# M452sx.net
KiCad netlist of a schematic drawn in EAGLE
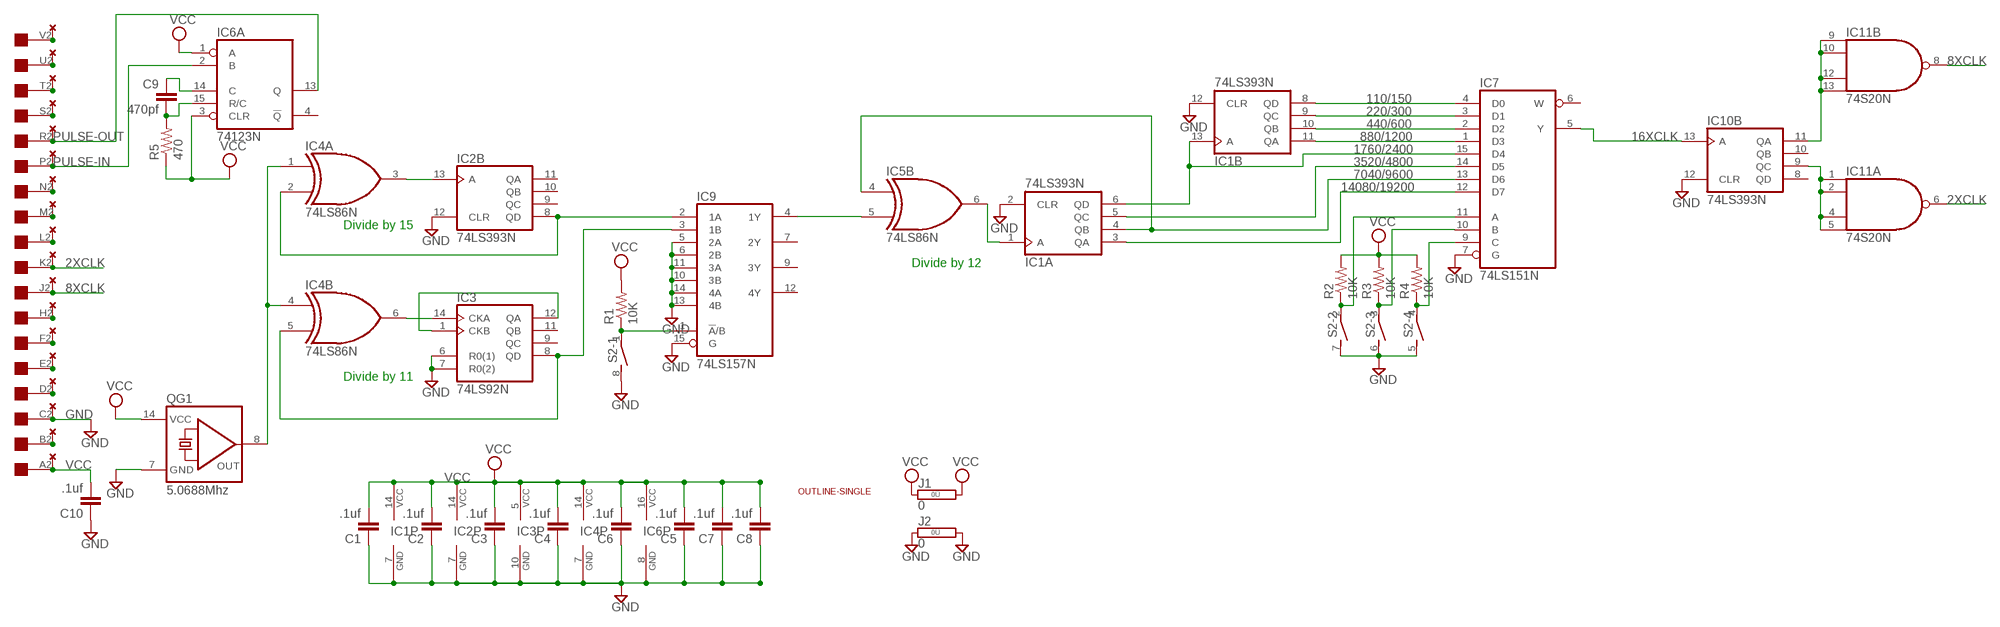
[diagram p0: schematic, sheet 1]

(export (version "E")
  (design (tool "Eeschema 10.0.6"))
  (components
    (comp (ref "C1")
      (value ".1uf")
      (footprint "eagle-import:C050-025X075")
      (libsource (lib "eagle-import") (part "C-EU050-025X075"))
    )
    (comp (ref "C2")
      (value ".1uf")
      (footprint "eagle-import:C050-025X075")
      (libsource (lib "eagle-import") (part "C-EU050-025X075"))
    )
    (comp (ref "C3")
      (value ".1uf")
      (footprint "eagle-import:C050-025X075")
      (libsource (lib "eagle-import") (part "C-EU050-025X075"))
    )
    (comp (ref "C4")
      (value ".1uf")
      (footprint "eagle-import:C050-025X075")
      (libsource (lib "eagle-import") (part "C-EU050-025X075"))
    )
    (comp (ref "C5")
      (value ".1uf")
      (footprint "eagle-import:C050-025X075")
      (libsource (lib "eagle-import") (part "C-EU050-025X075"))
    )
    (comp (ref "C6")
      (value ".1uf")
      (footprint "eagle-import:C050-025X075")
      (libsource (lib "eagle-import") (part "C-EU050-025X075"))
    )
    (comp (ref "C7")
      (value ".1uf")
      (footprint "eagle-import:C050-025X075")
      (libsource (lib "eagle-import") (part "C-EU050-025X075"))
    )
    (comp (ref "C8")
      (value ".1uf")
      (footprint "eagle-import:C050-025X075")
      (libsource (lib "eagle-import") (part "C-EU050-025X075"))
    )
    (comp (ref "C9")
      (value "470pf")
      (footprint "eagle-import:C050-025X075")
      (libsource (lib "eagle-import") (part "C-EU050-025X075"))
    )
    (comp (ref "C10")
      (value ".1uf")
      (footprint "eagle-import:C050-025X075")
      (libsource (lib "eagle-import") (part "C-EU050-025X075"))
    )
    (comp (ref "IC1")
      (value "74LS393N")
      (footprint "eagle-import:DIL14")
      (libsource (lib "eagle-import") (part "74393NLS"))
    )
    (comp (ref "IC2")
      (value "74LS393N")
      (footprint "eagle-import:DIL14")
      (libsource (lib "eagle-import") (part "74393NLS"))
    )
    (comp (ref "IC3")
      (value "74LS92N")
      (footprint "eagle-import:DIL14")
      (libsource (lib "eagle-import") (part "7492NLS"))
    )
    (comp (ref "IC4")
      (value "74LS86N")
      (footprint "eagle-import:DIL14")
      (libsource (lib "eagle-import") (part "7486NLS"))
    )
    (comp (ref "IC5")
      (value "74LS86N")
      (footprint "eagle-import:DIL14")
      (libsource (lib "eagle-import") (part "7486NLS"))
    )
    (comp (ref "IC6")
      (value "74123N")
      (footprint "eagle-import:DIL16")
      (libsource (lib "eagle-import") (part "74123N"))
    )
    (comp (ref "IC7")
      (value "74LS151N")
      (footprint "eagle-import:DIL16")
      (libsource (lib "eagle-import") (part "74151N"))
    )
    (comp (ref "IC9")
      (value "74LS157N")
      (footprint "eagle-import:DIL16")
      (libsource (lib "eagle-import") (part "74157NLS"))
    )
    (comp (ref "IC10")
      (value "74LS393N")
      (footprint "eagle-import:DIL14")
      (libsource (lib "eagle-import") (part "74393NLS"))
    )
    (comp (ref "IC11")
      (value "74S20N")
      (footprint "eagle-import:DIL14")
      (libsource (lib "eagle-import") (part "7420NS"))
    )
    (comp (ref "J1")
      (value "0")
      (footprint "eagle-import:0R_10")
      (libsource (lib "eagle-import") (part "0R"))
    )
    (comp (ref "J2")
      (value "0")
      (footprint "eagle-import:0R_10")
      (libsource (lib "eagle-import") (part "0R"))
    )
    (comp (ref "QG1")
      (value "5.0688Mhz")
      (footprint "eagle-import:DIL14S")
      (libsource (lib "eagle-import") (part "QG5860"))
    )
    (comp (ref "R1")
      (value "10K")
      (footprint "eagle-import:0204_7")
      (libsource (lib "eagle-import") (part "R-US_0204/7"))
    )
    (comp (ref "R2")
      (value "10K")
      (footprint "eagle-import:0204_7")
      (libsource (lib "eagle-import") (part "R-US_0204/7"))
    )
    (comp (ref "R3")
      (value "10K")
      (footprint "eagle-import:0204_7")
      (libsource (lib "eagle-import") (part "R-US_0204/7"))
    )
    (comp (ref "R4")
      (value "10K")
      (footprint "eagle-import:0204_7")
      (libsource (lib "eagle-import") (part "R-US_0204/7"))
    )
    (comp (ref "R5")
      (value "470")
      (footprint "eagle-import:0204_7")
      (libsource (lib "eagle-import") (part "R-US_0204/7"))
    )
    (comp (ref "S2")
      (value "DIP04S")
      (footprint "eagle-import:DIP04S")
      (libsource (lib "eagle-import") (part "DIP04S"))
    )
    (comp (ref "U$2")
      (value "THRU-HOLE1")
      (footprint "eagle-import:THRU-HOLE1")
      (libsource (lib "eagle-import") (part "THRU-HOLE1"))
    )
    (comp (ref "U$3")
      (value "OUTLINE-SINGLE")
      (footprint "eagle-import:SINGLE")
      (libsource (lib "eagle-import") (part "OUTLINE-SINGLE"))
    )
    (comp (ref "U$4")
      (value "EDGE-1")
      (footprint "eagle-import:EDGE-CON1")
      (libsource (lib "eagle-import") (part "EDGE-1"))
    )
  )
  (nets
    (net (code "1") (name "/2XCLK") (class "Default")
      (node (ref "IC11") (pin "6") (pinfunction "O_6") (pintype "output"))
      (node (ref "U$2") (pin "K2") (pinfunction "P$1_K2") (pintype "passive"))
      (node (ref "U$4") (pin "K2") (pinfunction "1_K2") (pintype "bidirectional"))
    )
    (net (code "2") (name "/8XCLK") (class "Default")
      (node (ref "IC11") (pin "8") (pinfunction "O_8") (pintype "output"))
      (node (ref "U$2") (pin "J2") (pinfunction "P$1_J2") (pintype "passive"))
      (node (ref "U$4") (pin "J2") (pinfunction "1_J2") (pintype "bidirectional"))
    )
    (net (code "3") (name "/16XCLK") (class "Default")
      (node (ref "IC10") (pin "13") (pinfunction "A_13") (pintype "input"))
      (node (ref "IC7") (pin "5") (pinfunction "Y_5") (pintype "output"))
    )
    (net (code "4") (name "/110{slash}150") (class "Default")
      (node (ref "IC1") (pin "8") (pinfunction "QD_8") (pintype "output"))
      (node (ref "IC7") (pin "4") (pinfunction "D0_4") (pintype "input"))
    )
    (net (code "5") (name "/220{slash}300") (class "Default")
      (node (ref "IC1") (pin "9") (pinfunction "QC_9") (pintype "output"))
      (node (ref "IC7") (pin "3") (pinfunction "D1_3") (pintype "input"))
    )
    (net (code "6") (name "/440{slash}600") (class "Default")
      (node (ref "IC1") (pin "10") (pinfunction "QB_10") (pintype "output"))
      (node (ref "IC7") (pin "2") (pinfunction "D2_2") (pintype "input"))
    )
    (net (code "7") (name "/880{slash}1200") (class "Default")
      (node (ref "IC1") (pin "11") (pinfunction "QA_11") (pintype "output"))
      (node (ref "IC7") (pin "1") (pinfunction "D3_1") (pintype "input"))
    )
    (net (code "8") (name "/1760{slash}2400") (class "Default")
      (node (ref "IC1") (pin "13") (pinfunction "A_13") (pintype "input"))
      (node (ref "IC1") (pin "6") (pinfunction "QD_6") (pintype "output"))
      (node (ref "IC7") (pin "15") (pinfunction "D4_15") (pintype "input"))
    )
    (net (code "9") (name "/3520{slash}4800") (class "Default")
      (node (ref "IC1") (pin "5") (pinfunction "QC_5") (pintype "output"))
      (node (ref "IC7") (pin "14") (pinfunction "D5_14") (pintype "input"))
    )
    (net (code "10") (name "/7040{slash}9600") (class "Default")
      (node (ref "IC1") (pin "4") (pinfunction "QB_4") (pintype "output"))
      (node (ref "IC5") (pin "4") (pinfunction "I0_4") (pintype "input"))
      (node (ref "IC7") (pin "13") (pinfunction "D6_13") (pintype "input"))
    )
    (net (code "11") (name "/14080{slash}19200") (class "Default")
      (node (ref "IC1") (pin "3") (pinfunction "QA_3") (pintype "output"))
      (node (ref "IC7") (pin "12") (pinfunction "D7_12") (pintype "input"))
    )
    (net (code "12") (name "/PULSE-IN") (class "Default")
      (node (ref "IC6") (pin "2") (pinfunction "B_2") (pintype "input"))
      (node (ref "U$2") (pin "P2") (pinfunction "P$1_P2") (pintype "passive"))
      (node (ref "U$4") (pin "P2") (pinfunction "1_P2") (pintype "bidirectional"))
    )
    (net (code "13") (name "/PULSE-OUT") (class "Default")
      (node (ref "IC6") (pin "13") (pinfunction "Q_13") (pintype "output"))
      (node (ref "U$2") (pin "R2") (pinfunction "P$1_R2") (pintype "passive"))
      (node (ref "U$4") (pin "R2") (pinfunction "1_R2") (pintype "bidirectional"))
    )
    (net (code "14") (name "GND") (class "Default")
      (node (ref "C1") (pin "1") (pinfunction "1_1") (pintype "passive"))
      (node (ref "C10") (pin "1") (pinfunction "1_1") (pintype "passive"))
      (node (ref "C2") (pin "1") (pinfunction "1_1") (pintype "passive"))
      (node (ref "C3") (pin "1") (pinfunction "1_1") (pintype "passive"))
      (node (ref "C4") (pin "1") (pinfunction "1_1") (pintype "passive"))
      (node (ref "C5") (pin "1") (pinfunction "1_1") (pintype "passive"))
      (node (ref "C6") (pin "1") (pinfunction "1_1") (pintype "passive"))
      (node (ref "C7") (pin "1") (pinfunction "1_1") (pintype "passive"))
      (node (ref "C8") (pin "1") (pinfunction "1_1") (pintype "passive"))
      (node (ref "IC1") (pin "12") (pinfunction "CLR_12") (pintype "input"))
      (node (ref "IC1") (pin "2") (pinfunction "CLR_2") (pintype "input"))
      (node (ref "IC1") (pin "7") (pinfunction "GND_7") (pintype "power_in"))
      (node (ref "IC10") (pin "12") (pinfunction "CLR_12") (pintype "input"))
      (node (ref "IC2") (pin "12") (pinfunction "CLR_12") (pintype "input"))
      (node (ref "IC2") (pin "7") (pinfunction "GND_7") (pintype "power_in"))
      (node (ref "IC3") (pin "10") (pinfunction "GND_10") (pintype "power_in"))
      (node (ref "IC3") (pin "6") (pinfunction "R0(1)_6") (pintype "input"))
      (node (ref "IC3") (pin "7") (pinfunction "R0(2)_7") (pintype "input"))
      (node (ref "IC4") (pin "7") (pinfunction "GND_7") (pintype "power_in"))
      (node (ref "IC6") (pin "8") (pinfunction "GND_8") (pintype "power_in"))
      (node (ref "IC7") (pin "7") (pinfunction "G_7") (pintype "input"))
      (node (ref "IC9") (pin "10") (pinfunction "3B_10") (pintype "input"))
      (node (ref "IC9") (pin "11") (pinfunction "3A_11") (pintype "input"))
      (node (ref "IC9") (pin "13") (pinfunction "4B_13") (pintype "input"))
      (node (ref "IC9") (pin "14") (pinfunction "4A_14") (pintype "input"))
      (node (ref "IC9") (pin "15") (pinfunction "G_15") (pintype "input"))
      (node (ref "IC9") (pin "5") (pinfunction "2A_5") (pintype "input"))
      (node (ref "IC9") (pin "6") (pinfunction "2B_6") (pintype "input"))
      (node (ref "J2") (pin "1") (pinfunction "1_1") (pintype "passive"))
      (node (ref "J2") (pin "2") (pinfunction "2_2") (pintype "passive"))
      (node (ref "QG1") (pin "7") (pinfunction "GND_7") (pintype "power_in"))
      (node (ref "S2") (pin "5") (pinfunction "2_5") (pintype "passive"))
      (node (ref "S2") (pin "6") (pinfunction "2_6") (pintype "passive"))
      (node (ref "S2") (pin "7") (pinfunction "2_7") (pintype "passive"))
      (node (ref "S2") (pin "8") (pinfunction "2_8") (pintype "passive"))
      (node (ref "U$2") (pin "C2") (pinfunction "P$1_C2") (pintype "passive"))
      (node (ref "U$4") (pin "C2") (pinfunction "1_C2") (pintype "bidirectional"))
    )
    (net (code "15") (name "Net-(IC1A-A)") (class "Default")
      (node (ref "IC1") (pin "1") (pinfunction "A_1") (pintype "input"))
      (node (ref "IC5") (pin "6") (pinfunction "O_6") (pintype "output"))
    )
    (net (code "16") (name "Net-(IC2B-A)") (class "Default")
      (node (ref "IC2") (pin "13") (pinfunction "A_13") (pintype "input"))
      (node (ref "IC4") (pin "3") (pinfunction "O_3") (pintype "output"))
    )
    (net (code "17") (name "Net-(IC2B-QD)") (class "Default")
      (node (ref "IC2") (pin "8") (pinfunction "QD_8") (pintype "output"))
      (node (ref "IC4") (pin "2") (pinfunction "I1_2") (pintype "input"))
      (node (ref "IC9") (pin "2") (pinfunction "1A_2") (pintype "input"))
    )
    (net (code "18") (name "Net-(IC3A-CKA)") (class "Default")
      (node (ref "IC3") (pin "14") (pinfunction "CKA_14") (pintype "input"))
      (node (ref "IC4") (pin "6") (pinfunction "O_6") (pintype "output"))
    )
    (net (code "19") (name "Net-(IC3A-CKB)") (class "Default")
      (node (ref "IC3") (pin "1") (pinfunction "CKB_1") (pintype "input"))
      (node (ref "IC3") (pin "12") (pinfunction "QA_12") (pintype "output"))
    )
    (net (code "20") (name "Net-(IC3A-QD)") (class "Default")
      (node (ref "IC3") (pin "8") (pinfunction "QD_8") (pintype "output"))
      (node (ref "IC4") (pin "5") (pinfunction "I1_5") (pintype "input"))
      (node (ref "IC9") (pin "3") (pinfunction "1B_3") (pintype "input"))
    )
    (net (code "21") (name "Net-(IC4A-I0)") (class "Default")
      (node (ref "IC4") (pin "1") (pinfunction "I0_1") (pintype "input"))
      (node (ref "IC4") (pin "4") (pinfunction "I0_4") (pintype "input"))
      (node (ref "QG1") (pin "8") (pinfunction "OUT_8") (pintype "output"))
    )
    (net (code "22") (name "Net-(IC5B-I1)") (class "Default")
      (node (ref "IC5") (pin "5") (pinfunction "I1_5") (pintype "input"))
      (node (ref "IC9") (pin "4") (pinfunction "1Y_4") (pintype "output"))
    )
    (net (code "23") (name "Net-(IC6A-C)") (class "Default")
      (node (ref "C9") (pin "1") (pinfunction "1_1") (pintype "passive"))
      (node (ref "IC6") (pin "14") (pinfunction "C_14") (pintype "input"))
    )
    (net (code "24") (name "Net-(IC6A-R{slash}C)") (class "Default")
      (node (ref "C9") (pin "2") (pinfunction "2_2") (pintype "passive"))
      (node (ref "IC6") (pin "15") (pinfunction "R/C_15") (pintype "input"))
      (node (ref "R5") (pin "2") (pinfunction "2_2") (pintype "passive"))
    )
    (net (code "25") (name "Net-(IC7A-A)") (class "Default")
      (node (ref "IC7") (pin "11") (pinfunction "A_11") (pintype "input"))
      (node (ref "R2") (pin "1") (pinfunction "1_1") (pintype "passive"))
      (node (ref "S2") (pin "2") (pinfunction "1_2") (pintype "passive"))
    )
    (net (code "26") (name "Net-(IC7A-B)") (class "Default")
      (node (ref "IC7") (pin "10") (pinfunction "B_10") (pintype "input"))
      (node (ref "R3") (pin "1") (pinfunction "1_1") (pintype "passive"))
      (node (ref "S2") (pin "3") (pinfunction "1_3") (pintype "passive"))
    )
    (net (code "27") (name "Net-(IC7A-C)") (class "Default")
      (node (ref "IC7") (pin "9") (pinfunction "C_9") (pintype "input"))
      (node (ref "R4") (pin "1") (pinfunction "1_1") (pintype "passive"))
      (node (ref "S2") (pin "4") (pinfunction "1_4") (pintype "passive"))
    )
    (net (code "28") (name "Net-(IC9A-~{A}{slash}B)") (class "Default")
      (node (ref "IC9") (pin "1") (pinfunction "~{A}/B_1") (pintype "input"))
      (node (ref "R1") (pin "1") (pinfunction "1_1") (pintype "passive"))
      (node (ref "S2") (pin "1") (pinfunction "1_1") (pintype "passive"))
    )
    (net (code "29") (name "Net-(IC10B-QA)") (class "Default")
      (node (ref "IC10") (pin "11") (pinfunction "QA_11") (pintype "output"))
      (node (ref "IC11") (pin "10") (pinfunction "I1_10") (pintype "input"))
      (node (ref "IC11") (pin "12") (pinfunction "I2_12") (pintype "input"))
      (node (ref "IC11") (pin "13") (pinfunction "I3_13") (pintype "input"))
      (node (ref "IC11") (pin "9") (pinfunction "I0_9") (pintype "input"))
    )
    (net (code "30") (name "Net-(IC10B-QC)") (class "Default")
      (node (ref "IC10") (pin "9") (pinfunction "QC_9") (pintype "output"))
      (node (ref "IC11") (pin "1") (pinfunction "I0_1") (pintype "input"))
      (node (ref "IC11") (pin "2") (pinfunction "I1_2") (pintype "input"))
      (node (ref "IC11") (pin "4") (pinfunction "I2_4") (pintype "input"))
      (node (ref "IC11") (pin "5") (pinfunction "I3_5") (pintype "input"))
    )
    (net (code "31") (name "Net-(U$2B-P$1)") (class "Default")
      (node (ref "U$2") (pin "B2") (pinfunction "P$1_B2") (pintype "passive"))
      (node (ref "U$4") (pin "B2") (pinfunction "1_B2") (pintype "bidirectional"))
    )
    (net (code "32") (name "Net-(U$2D-P$1)") (class "Default")
      (node (ref "U$2") (pin "D2") (pinfunction "P$1_D2") (pintype "passive"))
      (node (ref "U$4") (pin "D2") (pinfunction "1_D2") (pintype "bidirectional"))
    )
    (net (code "33") (name "Net-(U$2E-P$1)") (class "Default")
      (node (ref "U$2") (pin "E2") (pinfunction "P$1_E2") (pintype "passive"))
      (node (ref "U$4") (pin "E2") (pinfunction "1_E2") (pintype "bidirectional"))
    )
    (net (code "34") (name "Net-(U$2F-P$1)") (class "Default")
      (node (ref "U$2") (pin "F2") (pinfunction "P$1_F2") (pintype "passive"))
      (node (ref "U$4") (pin "F2") (pinfunction "1_F2") (pintype "bidirectional"))
    )
    (net (code "35") (name "Net-(U$2G-P$1)") (class "Default")
      (node (ref "U$2") (pin "H2") (pinfunction "P$1_H2") (pintype "passive"))
      (node (ref "U$4") (pin "H2") (pinfunction "1_H2") (pintype "bidirectional"))
    )
    (net (code "36") (name "Net-(U$2J-P$1)") (class "Default")
      (node (ref "U$2") (pin "L2") (pinfunction "P$1_L2") (pintype "passive"))
      (node (ref "U$4") (pin "L2") (pinfunction "1_L2") (pintype "bidirectional"))
    )
    (net (code "37") (name "Net-(U$2K-P$1)") (class "Default")
      (node (ref "U$2") (pin "M2") (pinfunction "P$1_M2") (pintype "passive"))
      (node (ref "U$4") (pin "M2") (pinfunction "1_M2") (pintype "bidirectional"))
    )
    (net (code "38") (name "Net-(U$2L-P$1)") (class "Default")
      (node (ref "U$2") (pin "N2") (pinfunction "P$1_N2") (pintype "passive"))
      (node (ref "U$4") (pin "N2") (pinfunction "1_N2") (pintype "bidirectional"))
    )
    (net (code "39") (name "Net-(U$2O-P$1)") (class "Default")
      (node (ref "U$2") (pin "S2") (pinfunction "P$1_S2") (pintype "passive"))
      (node (ref "U$4") (pin "S2") (pinfunction "1_S2") (pintype "bidirectional"))
    )
    (net (code "40") (name "Net-(U$2P-P$1)") (class "Default")
      (node (ref "U$2") (pin "T2") (pinfunction "P$1_T2") (pintype "passive"))
      (node (ref "U$4") (pin "T2") (pinfunction "1_T2") (pintype "bidirectional"))
    )
    (net (code "41") (name "Net-(U$2Q-P$1)") (class "Default")
      (node (ref "U$2") (pin "U2") (pinfunction "P$1_U2") (pintype "passive"))
      (node (ref "U$4") (pin "U2") (pinfunction "1_U2") (pintype "bidirectional"))
    )
    (net (code "42") (name "Net-(U$2R-P$1)") (class "Default")
      (node (ref "U$2") (pin "V2") (pinfunction "P$1_V2") (pintype "passive"))
      (node (ref "U$4") (pin "V2") (pinfunction "1_V2") (pintype "bidirectional"))
    )
    (net (code "43") (name "VCC") (class "Default")
      (node (ref "C1") (pin "2") (pinfunction "2_2") (pintype "passive"))
      (node (ref "C10") (pin "2") (pinfunction "2_2") (pintype "passive"))
      (node (ref "C2") (pin "2") (pinfunction "2_2") (pintype "passive"))
      (node (ref "C3") (pin "2") (pinfunction "2_2") (pintype "passive"))
      (node (ref "C4") (pin "2") (pinfunction "2_2") (pintype "passive"))
      (node (ref "C5") (pin "2") (pinfunction "2_2") (pintype "passive"))
      (node (ref "C6") (pin "2") (pinfunction "2_2") (pintype "passive"))
      (node (ref "C7") (pin "2") (pinfunction "2_2") (pintype "passive"))
      (node (ref "C8") (pin "2") (pinfunction "2_2") (pintype "passive"))
      (node (ref "IC1") (pin "14") (pinfunction "VCC_14") (pintype "power_in"))
      (node (ref "IC2") (pin "14") (pinfunction "VCC_14") (pintype "power_in"))
      (node (ref "IC3") (pin "5") (pinfunction "VCC_5") (pintype "power_in"))
      (node (ref "IC4") (pin "14") (pinfunction "VCC_14") (pintype "power_in"))
      (node (ref "IC6") (pin "1") (pinfunction "A_1") (pintype "input"))
      (node (ref "IC6") (pin "16") (pinfunction "VCC_16") (pintype "power_in"))
      (node (ref "IC6") (pin "3") (pinfunction "CLR_3") (pintype "input"))
      (node (ref "J1") (pin "1") (pinfunction "1_1") (pintype "passive"))
      (node (ref "J1") (pin "2") (pinfunction "2_2") (pintype "passive"))
      (node (ref "QG1") (pin "14") (pinfunction "VCC_14") (pintype "power_in"))
      (node (ref "R1") (pin "2") (pinfunction "2_2") (pintype "passive"))
      (node (ref "R2") (pin "2") (pinfunction "2_2") (pintype "passive"))
      (node (ref "R3") (pin "2") (pinfunction "2_2") (pintype "passive"))
      (node (ref "R4") (pin "2") (pinfunction "2_2") (pintype "passive"))
      (node (ref "R5") (pin "1") (pinfunction "1_1") (pintype "passive"))
      (node (ref "U$2") (pin "A2") (pinfunction "P$1_A2") (pintype "passive"))
      (node (ref "U$4") (pin "A2") (pinfunction "1_A2") (pintype "bidirectional"))
    )
    (net (code "44") (name "unconnected-(IC2B-QA-Pad11)") (class "Default")
      (node (ref "IC2") (pin "11") (pinfunction "QA_11") (pintype "output"))
    )
    (net (code "45") (name "unconnected-(IC2B-QB-Pad10)") (class "Default")
      (node (ref "IC2") (pin "10") (pinfunction "QB_10") (pintype "output"))
    )
    (net (code "46") (name "unconnected-(IC2B-QC-Pad9)") (class "Default")
      (node (ref "IC2") (pin "9") (pinfunction "QC_9") (pintype "output"))
    )
    (net (code "47") (name "unconnected-(IC3A-QB-Pad11)") (class "Default")
      (node (ref "IC3") (pin "11") (pinfunction "QB_11") (pintype "output"))
    )
    (net (code "48") (name "unconnected-(IC3A-QC-Pad9)") (class "Default")
      (node (ref "IC3") (pin "9") (pinfunction "QC_9") (pintype "output"))
    )
    (net (code "49") (name "unconnected-(IC6A-~{Q}-Pad4)") (class "Default")
      (node (ref "IC6") (pin "4") (pinfunction "~{Q}_4") (pintype "output"))
    )
    (net (code "50") (name "unconnected-(IC7A-W-Pad6)") (class "Default")
      (node (ref "IC7") (pin "6") (pinfunction "W_6") (pintype "output"))
    )
    (net (code "51") (name "unconnected-(IC9A-2Y-Pad7)") (class "Default")
      (node (ref "IC9") (pin "7") (pinfunction "2Y_7") (pintype "output"))
    )
    (net (code "52") (name "unconnected-(IC9A-3Y-Pad9)") (class "Default")
      (node (ref "IC9") (pin "9") (pinfunction "3Y_9") (pintype "output"))
    )
    (net (code "53") (name "unconnected-(IC9A-4Y-Pad12)") (class "Default")
      (node (ref "IC9") (pin "12") (pinfunction "4Y_12") (pintype "output"))
    )
    (net (code "54") (name "unconnected-(IC10B-QB-Pad10)") (class "Default")
      (node (ref "IC10") (pin "10") (pinfunction "QB_10") (pintype "output"))
    )
    (net (code "55") (name "unconnected-(IC10B-QD-Pad8)") (class "Default")
      (node (ref "IC10") (pin "8") (pinfunction "QD_8") (pintype "output"))
    )
  )
)
